# 22_-_PIXHAWK_CONNECTOR.net
KiCad netlist of a schematic drawn in Altium Designer
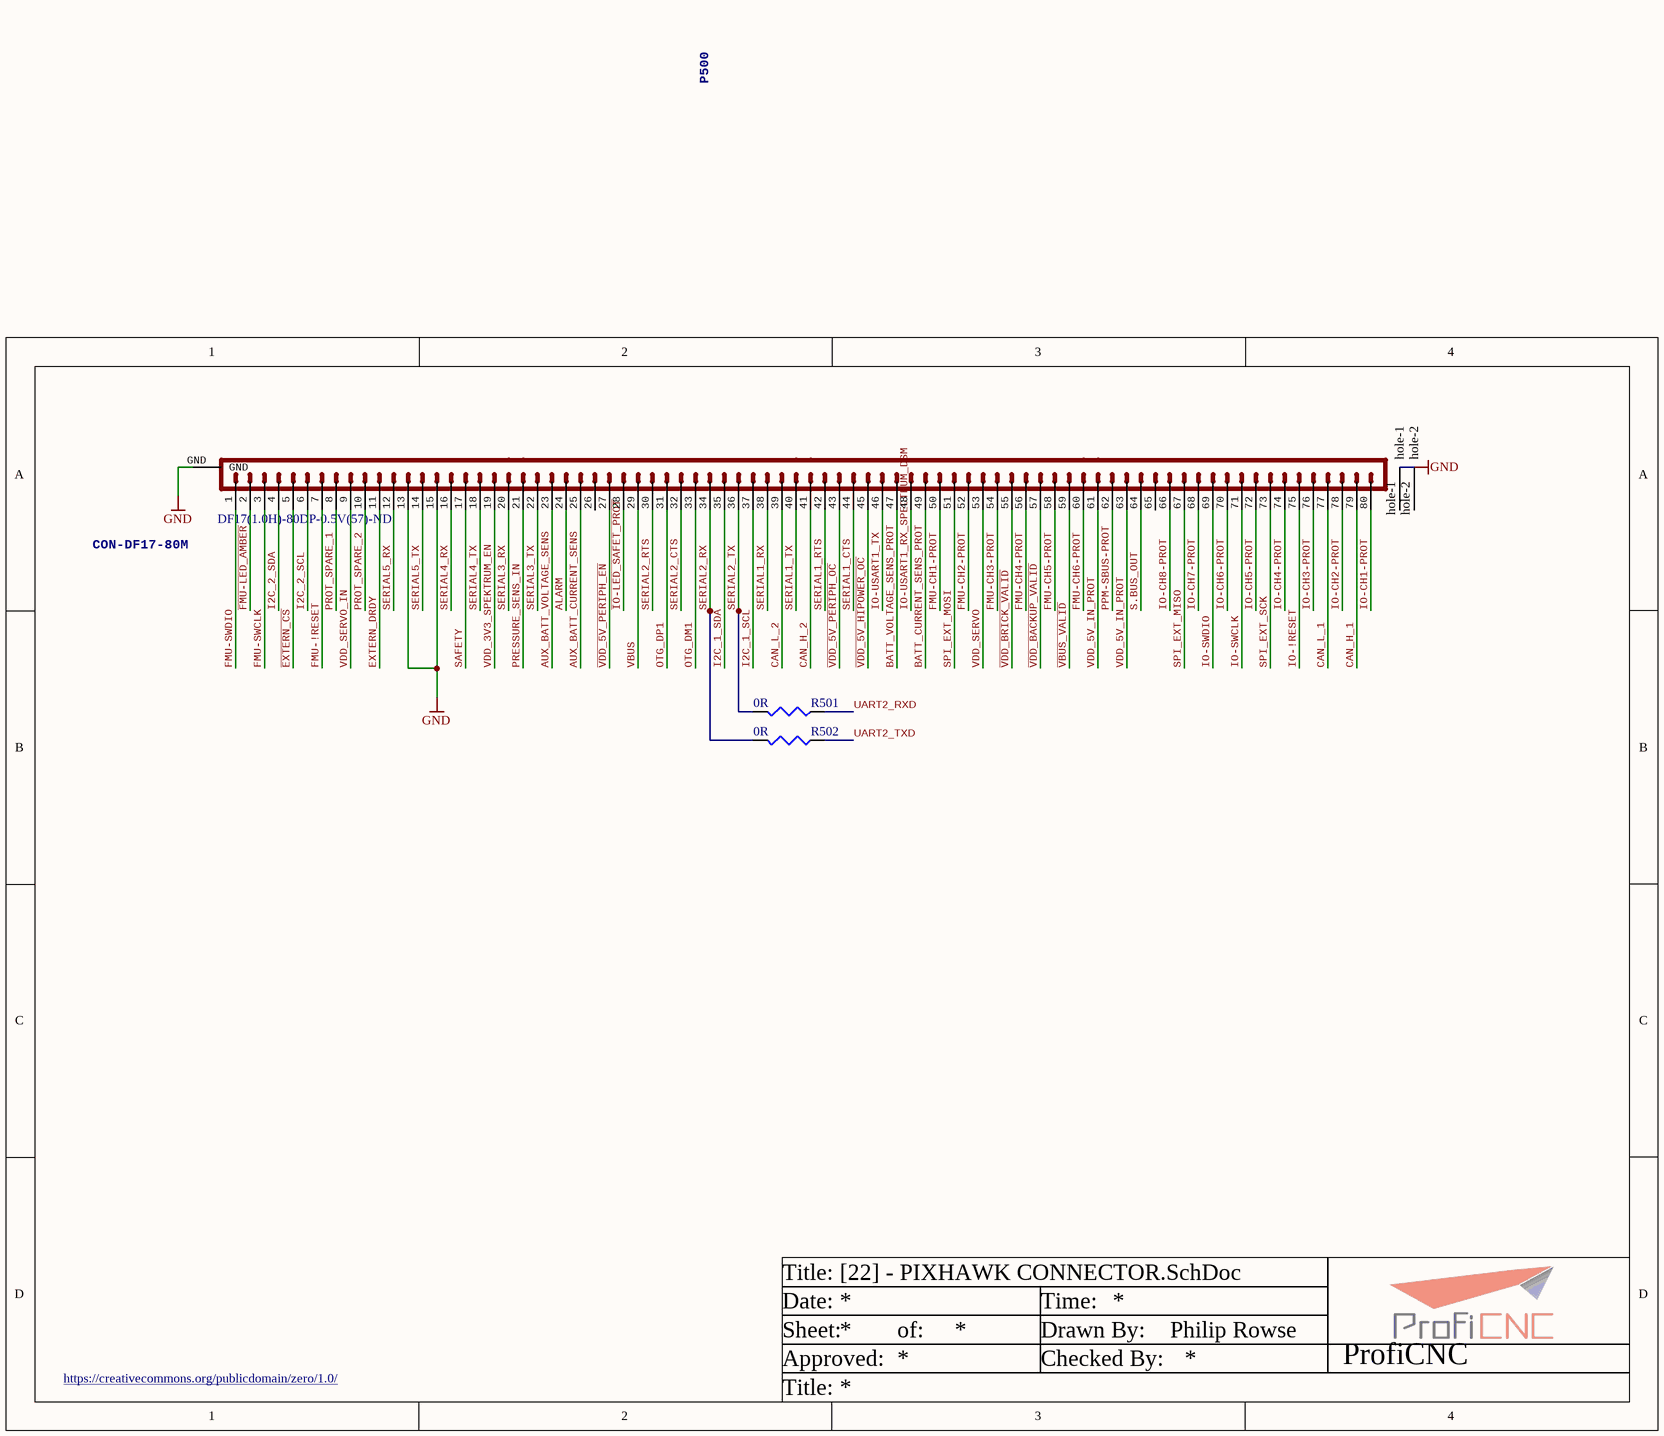
[diagram p0: [22] - PIXHAWK CONNECTOR.SchDoc]

(export (version "E")
  (design (tool "Eeschema 10.0.6"))
  (components
    (comp (ref "P500")
      (value "CON-DF17-80M")
      (footprint "CON-DF17-80M")
      (description "Connector, Header, 80Pos, .5MM, DUAL, SMD, Au")
      (fields
        (field (name "SUPPLIER PART NUMBER 1") "DF17(1.0H)-80DP-0.5V(57)-ND")
        (field (name "3DR_PARTNO") "PRT0436")
      )
      (libsource (lib "PCA_0005_FULL_CB_REV_A") (part "CON-DF17-80M"))
    )
    (comp (ref "R501")
      (value "0R")
      (footprint "R0402")
      (description "RES 0.0 OHM 1/16W 0402 SMD")
      (fields
        (field (name "MANUFACTURER") "Yageo")
        (field (name "MANUFACTURER PART NUMBER") "RC0402JR-070RL")
      )
      (libsource (lib "Integrated_Library_FEDEVEL_APR_2015") (part "RC0402JR-070RL"))
    )
    (comp (ref "R502")
      (value "0R")
      (footprint "R0402")
      (description "RES 0.0 OHM 1/16W 0402 SMD")
      (fields
        (field (name "MANUFACTURER") "Yageo")
        (field (name "MANUFACTURER PART NUMBER") "RC0402JR-070RL")
      )
      (libsource (lib "Integrated_Library_FEDEVEL_APR_2015") (part "RC0402JR-070RL"))
    )
  )
  (nets
    (net (code "1") (name "/ALARM") (class "Default")
      (node (ref "P500") (pin "24") (pinfunction "24_24") (pintype "passive"))
    )
    (net (code "2") (name "/AUX_BATT_CURRENT_SENS") (class "Default")
      (node (ref "P500") (pin "25") (pinfunction "25_25") (pintype "passive"))
    )
    (net (code "3") (name "/AUX_BATT_VOLTAGE_SENS") (class "Default")
      (node (ref "P500") (pin "23") (pinfunction "23_23") (pintype "passive"))
    )
    (net (code "4") (name "/BATT_CURRENT_SENS_PROT") (class "Default")
      (node (ref "P500") (pin "49") (pinfunction "49_49") (pintype "passive"))
    )
    (net (code "5") (name "/BATT_VOLTAGE_SENS_PROT") (class "Default")
      (node (ref "P500") (pin "47") (pinfunction "47_47") (pintype "passive"))
    )
    (net (code "6") (name "/CAN_H_1") (class "Default")
      (node (ref "P500") (pin "79") (pinfunction "79_79") (pintype "passive"))
    )
    (net (code "7") (name "/CAN_H_2") (class "Default")
      (node (ref "P500") (pin "41") (pinfunction "41_41") (pintype "passive"))
    )
    (net (code "8") (name "/CAN_L_1") (class "Default")
      (node (ref "P500") (pin "77") (pinfunction "77_77") (pintype "passive"))
    )
    (net (code "9") (name "/CAN_L_2") (class "Default")
      (node (ref "P500") (pin "39") (pinfunction "39_39") (pintype "passive"))
    )
    (net (code "10") (name "/EXTERN_DRDY") (class "Default")
      (node (ref "P500") (pin "11") (pinfunction "11_11") (pintype "passive"))
    )
    (net (code "11") (name "/FMU-!RESET") (class "Default")
      (node (ref "P500") (pin "7") (pinfunction "7_7") (pintype "passive"))
    )
    (net (code "12") (name "/FMU-CH1-PROT") (class "Default")
      (node (ref "P500") (pin "50") (pinfunction "50_50") (pintype "passive"))
    )
    (net (code "13") (name "/FMU-CH2-PROT") (class "Default")
      (node (ref "P500") (pin "52") (pinfunction "52_52") (pintype "passive"))
    )
    (net (code "14") (name "/FMU-CH3-PROT") (class "Default")
      (node (ref "P500") (pin "54") (pinfunction "54_54") (pintype "passive"))
    )
    (net (code "15") (name "/FMU-CH4-PROT") (class "Default")
      (node (ref "P500") (pin "56") (pinfunction "56_56") (pintype "passive"))
    )
    (net (code "16") (name "/FMU-CH5-PROT") (class "Default")
      (node (ref "P500") (pin "58") (pinfunction "58_58") (pintype "passive"))
    )
    (net (code "17") (name "/FMU-CH6-PROT") (class "Default")
      (node (ref "P500") (pin "60") (pinfunction "60_60") (pintype "passive"))
    )
    (net (code "18") (name "/FMU-SWCLK") (class "Default")
      (node (ref "P500") (pin "3") (pinfunction "3_3") (pintype "passive"))
    )
    (net (code "19") (name "/FMU-SWDIO") (class "Default")
      (node (ref "P500") (pin "1") (pinfunction "1_1") (pintype "passive"))
    )
    (net (code "20") (name "/I2C_1_SCL") (class "Default")
      (node (ref "P500") (pin "37") (pinfunction "37_37") (pintype "passive"))
    )
    (net (code "21") (name "/I2C_1_SDA") (class "Default")
      (node (ref "P500") (pin "35") (pinfunction "35_35") (pintype "passive"))
    )
    (net (code "22") (name "/I2C_2_SCL") (class "Default")
      (node (ref "P500") (pin "6") (pinfunction "6_6") (pintype "passive"))
    )
    (net (code "23") (name "/I2C_2_SDA") (class "Default")
      (node (ref "P500") (pin "4") (pinfunction "4_4") (pintype "passive"))
    )
    (net (code "24") (name "/IO-!RESET") (class "Default")
      (node (ref "P500") (pin "75") (pinfunction "75_75") (pintype "passive"))
    )
    (net (code "25") (name "/IO-CH1-PROT") (class "Default")
      (node (ref "P500") (pin "80") (pinfunction "80_80") (pintype "passive"))
    )
    (net (code "26") (name "/IO-CH2-PROT") (class "Default")
      (node (ref "P500") (pin "78") (pinfunction "78_78") (pintype "passive"))
    )
    (net (code "27") (name "/IO-CH3-PROT") (class "Default")
      (node (ref "P500") (pin "76") (pinfunction "76_76") (pintype "passive"))
    )
    (net (code "28") (name "/IO-CH4-PROT") (class "Default")
      (node (ref "P500") (pin "74") (pinfunction "74_74") (pintype "passive"))
    )
    (net (code "29") (name "/IO-CH5-PROT") (class "Default")
      (node (ref "P500") (pin "72") (pinfunction "72_72") (pintype "passive"))
    )
    (net (code "30") (name "/IO-CH6-PROT") (class "Default")
      (node (ref "P500") (pin "70") (pinfunction "70_70") (pintype "passive"))
    )
    (net (code "31") (name "/IO-CH7-PROT") (class "Default")
      (node (ref "P500") (pin "68") (pinfunction "68_68") (pintype "passive"))
    )
    (net (code "32") (name "/IO-CH8-PROT") (class "Default")
      (node (ref "P500") (pin "66") (pinfunction "66_66") (pintype "passive"))
    )
    (net (code "33") (name "/IO-SWCLK") (class "Default")
      (node (ref "P500") (pin "71") (pinfunction "71_71") (pintype "passive"))
    )
    (net (code "34") (name "/IO-SWDIO") (class "Default")
      (node (ref "P500") (pin "69") (pinfunction "69_69") (pintype "passive"))
    )
    (net (code "35") (name "/IO-USART1_RX_SPECTRUM_DSM") (class "Default")
      (node (ref "P500") (pin "48") (pinfunction "48_48") (pintype "passive"))
    )
    (net (code "36") (name "/IO-USART1_TX") (class "Default")
      (node (ref "P500") (pin "46") (pinfunction "46_46") (pintype "passive"))
    )
    (net (code "37") (name "/OTG_DM1") (class "Default")
      (node (ref "P500") (pin "33") (pinfunction "33_33") (pintype "passive"))
    )
    (net (code "38") (name "/OTG_DP1") (class "Default")
      (node (ref "P500") (pin "31") (pinfunction "31_31") (pintype "passive"))
    )
    (net (code "39") (name "/PPM-SBUS-PROT") (class "Default")
      (node (ref "P500") (pin "62") (pinfunction "62_62") (pintype "passive"))
    )
    (net (code "40") (name "/PRESSURE_SENS_IN") (class "Default")
      (node (ref "P500") (pin "21") (pinfunction "21_21") (pintype "passive"))
    )
    (net (code "41") (name "/PROT_SPARE_1") (class "Default")
      (node (ref "P500") (pin "8") (pinfunction "8_8") (pintype "passive"))
    )
    (net (code "42") (name "/PROT_SPARE_2") (class "Default")
      (node (ref "P500") (pin "10") (pinfunction "10_10") (pintype "passive"))
    )
    (net (code "43") (name "/S.BUS_OUT") (class "Default")
      (node (ref "P500") (pin "64") (pinfunction "64_64") (pintype "passive"))
    )
    (net (code "44") (name "/SAFETY") (class "Default")
      (node (ref "P500") (pin "17") (pinfunction "17_17") (pintype "passive"))
    )
    (net (code "45") (name "/SERIAL1_CTS") (class "Default")
      (node (ref "P500") (pin "44") (pinfunction "44_44") (pintype "passive"))
    )
    (net (code "46") (name "/SERIAL1_RTS") (class "Default")
      (node (ref "P500") (pin "42") (pinfunction "42_42") (pintype "passive"))
    )
    (net (code "47") (name "/SERIAL1_RX") (class "Default")
      (node (ref "P500") (pin "38") (pinfunction "38_38") (pintype "passive"))
    )
    (net (code "48") (name "/SERIAL1_TX") (class "Default")
      (node (ref "P500") (pin "40") (pinfunction "40_40") (pintype "passive"))
    )
    (net (code "49") (name "/SERIAL2_CTS") (class "Default")
      (node (ref "P500") (pin "32") (pinfunction "32_32") (pintype "passive"))
    )
    (net (code "50") (name "/SERIAL2_RTS") (class "Default")
      (node (ref "P500") (pin "30") (pinfunction "30_30") (pintype "passive"))
    )
    (net (code "51") (name "/SERIAL2_RX") (class "Default")
      (node (ref "P500") (pin "34") (pinfunction "34_34") (pintype "passive"))
      (node (ref "R502") (pin "2") (pinfunction "2_2") (pintype "passive"))
    )
    (net (code "52") (name "/SERIAL2_TX") (class "Default")
      (node (ref "P500") (pin "36") (pinfunction "36_36") (pintype "passive"))
      (node (ref "R501") (pin "2") (pinfunction "2_2") (pintype "passive"))
    )
    (net (code "53") (name "/SERIAL3_RX") (class "Default")
      (node (ref "P500") (pin "20") (pinfunction "20_20") (pintype "passive"))
    )
    (net (code "54") (name "/SERIAL3_TX") (class "Default")
      (node (ref "P500") (pin "22") (pinfunction "22_22") (pintype "passive"))
    )
    (net (code "55") (name "/SERIAL4_RX") (class "Default")
      (node (ref "P500") (pin "16") (pinfunction "16_16") (pintype "passive"))
    )
    (net (code "56") (name "/SERIAL4_TX") (class "Default")
      (node (ref "P500") (pin "18") (pinfunction "18_18") (pintype "passive"))
    )
    (net (code "57") (name "/SERIAL5_RX") (class "Default")
      (node (ref "P500") (pin "12") (pinfunction "12_12") (pintype "passive"))
    )
    (net (code "58") (name "/SERIAL5_TX") (class "Default")
      (node (ref "P500") (pin "14") (pinfunction "14_14") (pintype "passive"))
    )
    (net (code "59") (name "/SPI_EXT_MISO") (class "Default")
      (node (ref "P500") (pin "67") (pinfunction "67_67") (pintype "passive"))
    )
    (net (code "60") (name "/SPI_EXT_MOSI") (class "Default")
      (node (ref "P500") (pin "51") (pinfunction "51_51") (pintype "passive"))
    )
    (net (code "61") (name "/SPI_EXT_SCK") (class "Default")
      (node (ref "P500") (pin "73") (pinfunction "73_73") (pintype "passive"))
    )
    (net (code "62") (name "/UART2_RXD") (class "Default")
      (node (ref "R501") (pin "1") (pinfunction "1_1") (pintype "passive"))
    )
    (net (code "63") (name "/UART2_TXD") (class "Default")
      (node (ref "R502") (pin "1") (pinfunction "1_1") (pintype "passive"))
    )
    (net (code "64") (name "/VBUS") (class "Default")
      (node (ref "P500") (pin "29") (pinfunction "29_29") (pintype "passive"))
    )
    (net (code "65") (name "/VDD_3V3_SPEKTRUM_EN") (class "Default")
      (node (ref "P500") (pin "19") (pinfunction "19_19") (pintype "passive"))
    )
    (net (code "66") (name "/VDD_5V_IN_PROT") (class "Default")
      (node (ref "P500") (pin "61") (pinfunction "61_61") (pintype "passive"))
      (node (ref "P500") (pin "63") (pinfunction "63_63") (pintype "passive"))
    )
    (net (code "67") (name "/VDD_SERVO") (class "Default")
      (node (ref "P500") (pin "53") (pinfunction "53_53") (pintype "passive"))
    )
    (net (code "68") (name "/VDD_SERVO_IN") (class "Default")
      (node (ref "P500") (pin "9") (pinfunction "9_9") (pintype "passive"))
    )
    (net (code "69") (name "/~{EXTERN_CS}") (class "Default")
      (node (ref "P500") (pin "5") (pinfunction "5_5") (pintype "passive"))
    )
    (net (code "70") (name "/~{FMU-LED_AMBER}") (class "Default")
      (node (ref "P500") (pin "2") (pinfunction "2_2") (pintype "passive"))
    )
    (net (code "71") (name "/~{IO-LED_SAFET_PROT}") (class "Default")
      (node (ref "P500") (pin "28") (pinfunction "28_28") (pintype "passive"))
    )
    (net (code "72") (name "/~{VBUS_VALID}") (class "Default")
      (node (ref "P500") (pin "59") (pinfunction "59_59") (pintype "passive"))
    )
    (net (code "73") (name "/~{VDD_5V_HIPOWER_OC}") (class "Default")
      (node (ref "P500") (pin "45") (pinfunction "45_45") (pintype "passive"))
    )
    (net (code "74") (name "/~{VDD_5V_PERIPH_EN}") (class "Default")
      (node (ref "P500") (pin "27") (pinfunction "27_27") (pintype "passive"))
    )
    (net (code "75") (name "/~{VDD_5V_PERIPH_OC}") (class "Default")
      (node (ref "P500") (pin "43") (pinfunction "43_43") (pintype "passive"))
    )
    (net (code "76") (name "/~{VDD_BACKUP_VALID}") (class "Default")
      (node (ref "P500") (pin "57") (pinfunction "57_57") (pintype "passive"))
    )
    (net (code "77") (name "/~{VDD_BRICK_VALID}") (class "Default")
      (node (ref "P500") (pin "55") (pinfunction "55_55") (pintype "passive"))
    )
    (net (code "78") (name "GND") (class "Default")
      (node (ref "P500") (pin "13") (pinfunction "13_13") (pintype "passive"))
      (node (ref "P500") (pin "15") (pinfunction "15_15") (pintype "passive"))
      (node (ref "P500") (pin "GND") (pinfunction "GND_GND") (pintype "passive"))
    )
    (net (code "79") (name "unconnected-(P500-Pad26)") (class "Default")
      (node (ref "P500") (pin "26") (pinfunction "26_26") (pintype "passive"))
    )
    (net (code "80") (name "unconnected-(P500-Pad65)") (class "Default")
      (node (ref "P500") (pin "65") (pinfunction "65_65") (pintype "passive"))
    )
    (net (code "81") (name "unconnected-(P500-Padhole-1)") (class "Default")
      (node (ref "P500") (pin "hole-1") (pinfunction "hole-1_hole-1") (pintype "passive"))
    )
    (net (code "82") (name "unconnected-(P500-Padhole-2)") (class "Default")
      (node (ref "P500") (pin "hole-2") (pinfunction "hole-2_hole-2") (pintype "passive"))
    )
  )
)
